# encoder.net
KiCad netlist of a schematic drawn in EAGLE
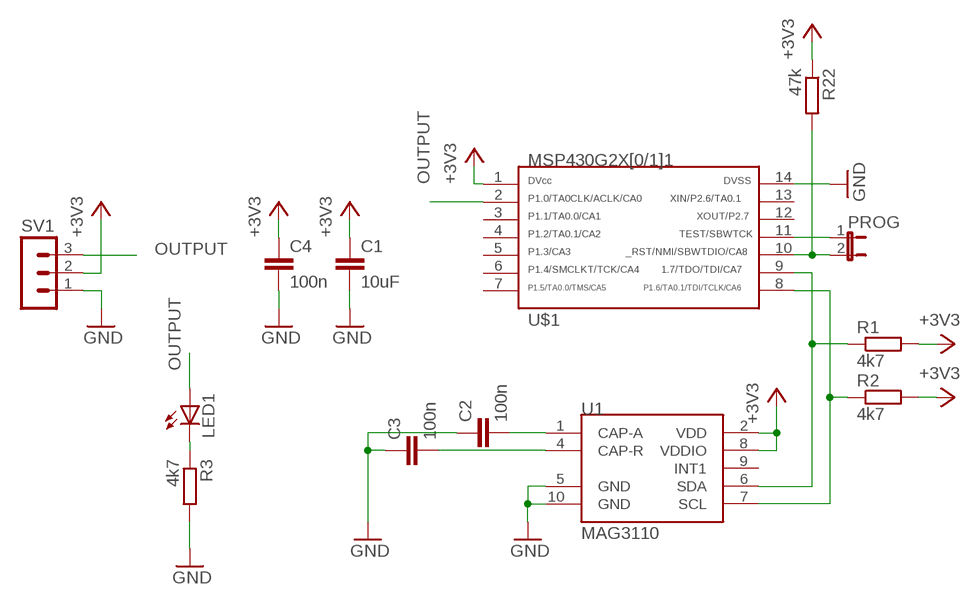
[diagram p0: schematic, sheet 1]

(export (version "E")
  (design (tool "Eeschema 10.0.6"))
  (components
    (comp (ref "C1")
      (value "10uF")
      (footprint "eagle-import:C0805")
      (libsource (lib "eagle-import") (part "C-EUC0805"))
    )
    (comp (ref "C2")
      (value "100n")
      (footprint "eagle-import:C0805")
      (libsource (lib "eagle-import") (part "C-EUC0805"))
    )
    (comp (ref "C3")
      (value "100n")
      (footprint "eagle-import:C0805")
      (libsource (lib "eagle-import") (part "C-EUC0805"))
    )
    (comp (ref "C4")
      (value "100n")
      (footprint "eagle-import:C0805")
      (libsource (lib "eagle-import") (part "C-EUC0805"))
    )
    (comp (ref "LED1")
      (value "LEDSML1206")
      (footprint "eagle-import:SML1206")
      (libsource (lib "eagle-import") (part "LEDSML1206"))
    )
    (comp (ref "PROG")
      (value "JP1E")
      (footprint "eagle-import:JP1")
      (libsource (lib "eagle-import") (part "JP1E"))
    )
    (comp (ref "R1")
      (value "4k7")
      (footprint "eagle-import:M0805")
      (libsource (lib "eagle-import") (part "R-EU_M0805"))
    )
    (comp (ref "R2")
      (value "4k7")
      (footprint "eagle-import:M0805")
      (libsource (lib "eagle-import") (part "R-EU_M0805"))
    )
    (comp (ref "R3")
      (value "4k7")
      (footprint "eagle-import:M0805")
      (libsource (lib "eagle-import") (part "R-EU_M0805"))
    )
    (comp (ref "R22")
      (value "47k")
      (footprint "eagle-import:M0805")
      (libsource (lib "eagle-import") (part "R-EU_M0805"))
    )
    (comp (ref "SV1")
      (value "MA03-1")
      (footprint "eagle-import:MA03-1")
      (libsource (lib "eagle-import") (part "MA03-1"))
    )
    (comp (ref "U$1")
      (value "G2X[0/1]1---PW14")
      (footprint "eagle-import:PW14")
      (libsource (lib "eagle-import") (part "G2X[0/1]1---PW14"))
    )
    (comp (ref "U1")
      (value "MAG3110")
      (footprint "eagle-import:DFN-10")
      (libsource (lib "eagle-import") (part "MAG3110"))
    )
  )
  (nets
    (net (code "1") (name "+3V3") (class "Default")
      (node (ref "C1") (pin "1") (pinfunction "1_1") (pintype "passive"))
      (node (ref "C4") (pin "1") (pinfunction "1_1") (pintype "passive"))
      (node (ref "R1") (pin "2") (pinfunction "2_2") (pintype "passive"))
      (node (ref "R2") (pin "2") (pinfunction "2_2") (pintype "passive"))
      (node (ref "R22") (pin "1") (pinfunction "1_1") (pintype "passive"))
      (node (ref "SV1") (pin "2") (pinfunction "2_2") (pintype "passive"))
      (node (ref "U$1") (pin "1") (pinfunction "1_1") (pintype "bidirectional"))
      (node (ref "U1") (pin "2") (pinfunction "VDD_2") (pintype "bidirectional"))
      (node (ref "U1") (pin "8") (pinfunction "VDDIO_8") (pintype "bidirectional"))
    )
    (net (code "2") (name "/OUTPUT") (class "Default")
      (node (ref "LED1") (pin "A") (pinfunction "A_A") (pintype "passive"))
      (node (ref "SV1") (pin "3") (pinfunction "3_3") (pintype "passive"))
      (node (ref "U$1") (pin "2") (pinfunction "2_2") (pintype "bidirectional"))
    )
    (net (code "3") (name "GND") (class "Default")
      (node (ref "C1") (pin "2") (pinfunction "2_2") (pintype "passive"))
      (node (ref "C2") (pin "1") (pinfunction "1_1") (pintype "passive"))
      (node (ref "C3") (pin "1") (pinfunction "1_1") (pintype "passive"))
      (node (ref "C4") (pin "2") (pinfunction "2_2") (pintype "passive"))
      (node (ref "R3") (pin "2") (pinfunction "2_2") (pintype "passive"))
      (node (ref "SV1") (pin "1") (pinfunction "1_1") (pintype "passive"))
      (node (ref "U$1") (pin "14") (pinfunction "14_14") (pintype "bidirectional"))
      (node (ref "U1") (pin "10") (pinfunction "GND_10") (pintype "bidirectional"))
      (node (ref "U1") (pin "5") (pinfunction "GND_5") (pintype "bidirectional"))
    )
    (net (code "4") (name "Net-(LED1-PadC)") (class "Default")
      (node (ref "LED1") (pin "C") (pinfunction "C_C") (pintype "passive"))
      (node (ref "R3") (pin "1") (pinfunction "1_1") (pintype "passive"))
    )
    (net (code "5") (name "Net-(PROG-Pad1)") (class "Default")
      (node (ref "PROG") (pin "1") (pinfunction "1_1") (pintype "passive"))
      (node (ref "U$1") (pin "11") (pinfunction "11_11") (pintype "bidirectional"))
    )
    (net (code "6") (name "Net-(PROG-Pad2)") (class "Default")
      (node (ref "PROG") (pin "2") (pinfunction "2_2") (pintype "passive"))
      (node (ref "R22") (pin "2") (pinfunction "2_2") (pintype "passive"))
      (node (ref "U$1") (pin "10") (pinfunction "10_10") (pintype "bidirectional"))
    )
    (net (code "7") (name "Net-(U1-CAP-A)") (class "Default")
      (node (ref "C2") (pin "2") (pinfunction "2_2") (pintype "passive"))
      (node (ref "U1") (pin "1") (pinfunction "CAP-A_1") (pintype "bidirectional"))
    )
    (net (code "8") (name "Net-(U1-CAP-R)") (class "Default")
      (node (ref "C3") (pin "2") (pinfunction "2_2") (pintype "passive"))
      (node (ref "U1") (pin "4") (pinfunction "CAP-R_4") (pintype "bidirectional"))
    )
    (net (code "9") (name "Net-(U1-SCL)") (class "Default")
      (node (ref "R2") (pin "1") (pinfunction "1_1") (pintype "passive"))
      (node (ref "U$1") (pin "8") (pinfunction "8_8") (pintype "bidirectional"))
      (node (ref "U1") (pin "7") (pinfunction "SCL_7") (pintype "bidirectional"))
    )
    (net (code "10") (name "Net-(U1-SDA)") (class "Default")
      (node (ref "R1") (pin "1") (pinfunction "1_1") (pintype "passive"))
      (node (ref "U$1") (pin "9") (pinfunction "9_9") (pintype "bidirectional"))
      (node (ref "U1") (pin "6") (pinfunction "SDA_6") (pintype "bidirectional"))
    )
    (net (code "11") (name "unconnected-(U$1-Pad3)") (class "Default")
      (node (ref "U$1") (pin "3") (pinfunction "3_3") (pintype "bidirectional"))
    )
    (net (code "12") (name "unconnected-(U$1-Pad4)") (class "Default")
      (node (ref "U$1") (pin "4") (pinfunction "4_4") (pintype "bidirectional"))
    )
    (net (code "13") (name "unconnected-(U$1-Pad5)") (class "Default")
      (node (ref "U$1") (pin "5") (pinfunction "5_5") (pintype "bidirectional"))
    )
    (net (code "14") (name "unconnected-(U$1-Pad6)") (class "Default")
      (node (ref "U$1") (pin "6") (pinfunction "6_6") (pintype "bidirectional"))
    )
    (net (code "15") (name "unconnected-(U$1-Pad7)") (class "Default")
      (node (ref "U$1") (pin "7") (pinfunction "7_7") (pintype "bidirectional"))
    )
    (net (code "16") (name "unconnected-(U$1-Pad12)") (class "Default")
      (node (ref "U$1") (pin "12") (pinfunction "12_12") (pintype "bidirectional"))
    )
    (net (code "17") (name "unconnected-(U$1-Pad13)") (class "Default")
      (node (ref "U$1") (pin "13") (pinfunction "13_13") (pintype "bidirectional"))
    )
    (net (code "18") (name "unconnected-(U1-INT1-Pad9)") (class "Default")
      (node (ref "U1") (pin "9") (pinfunction "INT1_9") (pintype "bidirectional"))
    )
  )
)
